# 4_Button.net
KiCad netlist of a schematic drawn in Altium Designer
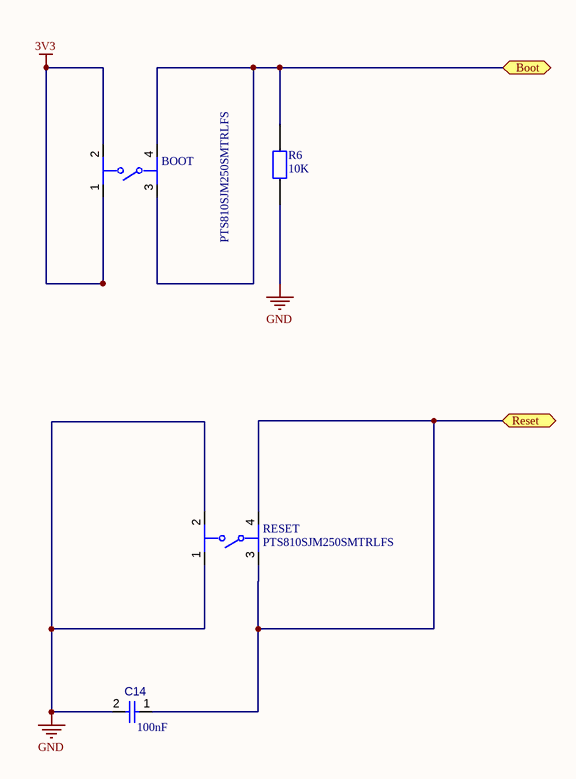
[diagram p0: [4]Button.SchDoc]

(export (version "E")
  (design (tool "Eeschema 10.0.6"))
  (components
    (comp (ref "BOOT")
      (value "PTS810SJM250SMTRLFS")
      (footprint "FP-PTS810SJM250SMTRLFS-MFG")
      (description "SWITCH TACTILE SPST-NO 0.05A 16V")
      (fields
        (field (name "OCTOPART") "https://octopart.com/pts810+sjm+250+smtr+lfs-c%26k+components-29687929")
        (field (name "MANUFACTURER") "C&K Components")
      )
      (libsource (lib "Schlib_For_High_Voltage_Sensor") (part "Button"))
    )
    (comp (ref "C14")
      (value "100nF")
      (footprint "CAPC1608X90X40ML10T20")
      (description "Chip Capacitor, 100 nF, +/- 10%, 50 V, 0603 (1608 Metric)")
      (fields (field (name "TOLERANCE") "10%") (field (name "Comment") "Capacitor 100 nF +/-10% 50 V 0603"))
      (libsource (lib "Latium Technologies") (part "CAP-NP-2"))
    )
    (comp (ref "R6")
      (value "10K")
      (footprint "RESC0603")
      (description "RES SMD 10K OHM 1% 1/4W 0603")
      (fields
        (field (name "MANUFACTURER") "Panasonic Electronic Components")
        (field (name "MANUFACTURER PART NUMBER") "ERJ-PA3F1002V")
      )
      (libsource (lib "Schlib_For_High_Voltage_Sensor") (part "ERJ-PA3F1002V"))
    )
    (comp (ref "RESET")
      (value "PTS810SJM250SMTRLFS")
      (footprint "FP-PTS810SJM250SMTRLFS-MFG")
      (description "SWITCH TACTILE SPST-NO 0.05A 16V")
      (fields
        (field (name "OCTOPART") "https://octopart.com/pts810+sjm+250+smtr+lfs-c%26k+components-29687929")
        (field (name "MANUFACTURER") "C&K Components")
      )
      (libsource (lib "Schlib_For_High_Voltage_Sensor") (part "Button"))
    )
  )
  (nets
    (net (code "1") (name "/Boot") (class "Default")
      (node (ref "BOOT") (pin "3") (pinfunction "3_3") (pintype "passive"))
      (node (ref "BOOT") (pin "4") (pinfunction "4_4") (pintype "passive"))
      (node (ref "R6") (pin "2") (pinfunction "2_2") (pintype "passive"))
    )
    (net (code "2") (name "/Reset") (class "Default")
      (node (ref "C14") (pin "1") (pinfunction "1_1") (pintype "passive"))
      (node (ref "RESET") (pin "3") (pinfunction "3_3") (pintype "passive"))
      (node (ref "RESET") (pin "4") (pinfunction "4_4") (pintype "passive"))
    )
    (net (code "3") (name "3V3") (class "Default")
      (node (ref "BOOT") (pin "1") (pinfunction "1_1") (pintype "passive"))
      (node (ref "BOOT") (pin "2") (pinfunction "2_2") (pintype "passive"))
    )
    (net (code "4") (name "GND") (class "Default")
      (node (ref "C14") (pin "2") (pinfunction "2_2") (pintype "passive"))
      (node (ref "R6") (pin "1") (pinfunction "1_1") (pintype "passive"))
      (node (ref "RESET") (pin "1") (pinfunction "1_1") (pintype "passive"))
      (node (ref "RESET") (pin "2") (pinfunction "2_2") (pintype "passive"))
    )
  )
)
